# CC_v00.net
KiCad netlist of a schematic drawn in Altium Designer
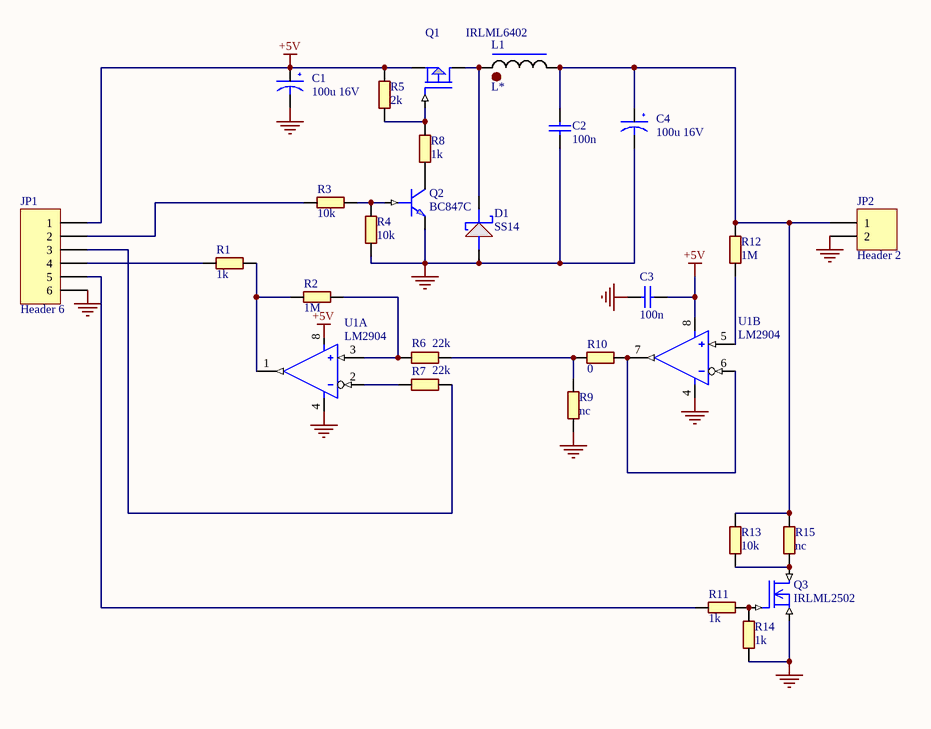
[diagram p0: CC_v00.SchDoc]

(export (version "E")
  (design (tool "Eeschema 10.0.6"))
  (components
    (comp (ref "C1")
      (value "100u 16V")
      (footprint "CAPPRD200W50D600H1250")
      (libsource (lib "Discrete") (part "C-EL-DIP"))
    )
    (comp (ref "C2") (value "100n") (footprint "CAPC1608X08N") (libsource (lib "Discrete") (part "CAPN")))
    (comp (ref "C3") (value "100n") (footprint "CAPC1608X08N") (libsource (lib "Discrete") (part "CAPN")))
    (comp (ref "C4")
      (value "100u 16V")
      (footprint "CAPPRD200W50D600H1250")
      (libsource (lib "Discrete") (part "C-EL-DIP"))
    )
    (comp (ref "D1")
      (value "SS14")
      (footprint "DIOM521X260X241L114X145N")
      (libsource (lib "Discrete") (part "DIODE SCHOTTKY"))
    )
    (comp (ref "JP1")
      (value "Header 6")
      (footprint "HDRV6W70P254_6X1_1397X254H754")
      (description "Header, 6-Pin")
      (fields (field (name "PUBLISHER") "Altium Limited"))
      (libsource (lib "Miscellaneous Connectors") (part "Header 6"))
    )
    (comp (ref "JP2")
      (value "Header 2")
      (footprint "HDRV2W64P254_2X1_508X254H854")
      (description "Header, 2-Pin")
      (fields (field (name "PUBLISHER") "Altium Limited"))
      (libsource (lib "Miscellaneous Connectors") (part "Header 2"))
    )
    (comp (ref "L1") (value "L*") (footprint "SND-0705") (libsource (lib "Discrete") (part "L*")))
    (comp (ref "Q1") (value "IRLML6402") (footprint "SOT-23") (libsource (lib "Discrete") (part "MOSF-P")))
    (comp (ref "Q2")
      (value "BC847C")
      (footprint "SOT95P245X110-3N")
      (libsource (lib "Discrete") (part "NPN"))
    )
    (comp (ref "Q3")
      (value "IRLML2502")
      (footprint "SOT95P245X110-3N")
      (libsource (lib "Discrete") (part "MFET N"))
    )
    (comp (ref "R1") (value "1k") (footprint "RESC1608X06N") (libsource (lib "Discrete") (part "RES")))
    (comp (ref "R2") (value "1M") (footprint "RESC1608X06N") (libsource (lib "Discrete") (part "RES")))
    (comp (ref "R3") (value "10k") (footprint "RESC1608X06N") (libsource (lib "Discrete") (part "RES")))
    (comp (ref "R4") (value "10k") (footprint "RESC1608X06N") (libsource (lib "") (part "RES_1")))
    (comp (ref "R5") (value "2k") (footprint "RESC1608X06N") (libsource (lib "") (part "RES_2")))
    (comp (ref "R6") (value "22k") (footprint "RESC1608X06N") (libsource (lib "Discrete") (part "RES")))
    (comp (ref "R7") (value "22k") (footprint "RESC1608X06N") (libsource (lib "Discrete") (part "RES")))
    (comp (ref "R8") (value "1k") (footprint "RESC1608X06N") (libsource (lib "") (part "RES_2")))
    (comp (ref "R9") (value "nc") (footprint "RESC1608X06N") (libsource (lib "") (part "RES_1")))
    (comp (ref "R10") (value "0") (footprint "RESC1608X06N") (libsource (lib "Discrete") (part "RES")))
    (comp (ref "R11") (value "1k") (footprint "RESC1608X06N") (libsource (lib "Discrete") (part "RES")))
    (comp (ref "R12") (value "1M") (footprint "RESC1608X06N") (libsource (lib "") (part "RES_2")))
    (comp (ref "R13") (value "10k") (footprint "RESC1608X06N") (libsource (lib "") (part "RES_2")))
    (comp (ref "R14") (value "1k") (footprint "RESC1608X06N") (libsource (lib "") (part "RES_2")))
    (comp (ref "R15") (value "nc") (footprint "RESC1608X06N") (libsource (lib "") (part "RES_2")))
    (comp (ref "U1")
      (value "LM2904")
      (footprint "SOIC127P600X175-8N")
      (description "2 Operation amplifier")
      (libsource (lib "ICs") (part "LM2904"))
    )
  )
  (nets
    (net (code "1") (name "+5V") (class "Default")
      (node (ref "C1") (pin "2") (pinfunction "+_2") (pintype "passive"))
      (node (ref "C3") (pin "2") (pinfunction "2_2") (pintype "passive"))
      (node (ref "JP1") (pin "1") (pinfunction "1_1") (pintype "passive"))
      (node (ref "Q1") (pin "3") (pinfunction "SOURCE_3") (pintype "passive"))
      (node (ref "R5") (pin "2") (pinfunction "2_2") (pintype "passive"))
      (node (ref "U1") (pin "8") (pinfunction "V+_8") (pintype "passive"))
    )
    (net (code "2") (name "GND") (class "Default")
      (node (ref "C1") (pin "1") (pinfunction "-_1") (pintype "passive"))
      (node (ref "C2") (pin "2") (pinfunction "2_2") (pintype "passive"))
      (node (ref "C3") (pin "1") (pinfunction "1_1") (pintype "passive"))
      (node (ref "C4") (pin "1") (pinfunction "-_1") (pintype "passive"))
      (node (ref "D1") (pin "A") (pinfunction "A_A") (pintype "passive"))
      (node (ref "JP1") (pin "6") (pinfunction "6_6") (pintype "passive"))
      (node (ref "JP2") (pin "2") (pinfunction "2_2") (pintype "passive"))
      (node (ref "Q2") (pin "3") (pinfunction "EMITTER_3") (pintype "passive"))
      (node (ref "Q3") (pin "3") (pinfunction "S_3") (pintype "input"))
      (node (ref "R14") (pin "1") (pinfunction "1_1") (pintype "passive"))
      (node (ref "R4") (pin "2") (pinfunction "2_2") (pintype "passive"))
      (node (ref "R9") (pin "2") (pinfunction "2_2") (pintype "passive"))
      (node (ref "U1") (pin "4") (pinfunction "V-_4") (pintype "power_in"))
    )
    (net (code "3") (name "Net-(C4-+)") (class "Default")
      (node (ref "C2") (pin "1") (pinfunction "1_1") (pintype "passive"))
      (node (ref "C4") (pin "2") (pinfunction "+_2") (pintype "passive"))
      (node (ref "JP2") (pin "1") (pinfunction "1_1") (pintype "passive"))
      (node (ref "L1") (pin "2") (pinfunction "2_2") (pintype "passive"))
      (node (ref "R12") (pin "2") (pinfunction "2_2") (pintype "passive"))
      (node (ref "R13") (pin "2") (pinfunction "2_2") (pintype "passive"))
      (node (ref "R15") (pin "2") (pinfunction "2_2") (pintype "passive"))
    )
    (net (code "4") (name "Net-(JP1-Pad2)") (class "Default")
      (node (ref "JP1") (pin "2") (pinfunction "2_2") (pintype "passive"))
      (node (ref "R3") (pin "2") (pinfunction "2_2") (pintype "passive"))
    )
    (net (code "5") (name "Net-(JP1-Pad3)") (class "Default")
      (node (ref "JP1") (pin "3") (pinfunction "3_3") (pintype "passive"))
      (node (ref "R7") (pin "1") (pinfunction "1_1") (pintype "passive"))
    )
    (net (code "6") (name "Net-(JP1-Pad4)") (class "Default")
      (node (ref "JP1") (pin "4") (pinfunction "4_4") (pintype "passive"))
      (node (ref "R1") (pin "2") (pinfunction "2_2") (pintype "passive"))
    )
    (net (code "7") (name "Net-(JP1-Pad5)") (class "Default")
      (node (ref "JP1") (pin "5") (pinfunction "5_5") (pintype "passive"))
      (node (ref "R11") (pin "2") (pinfunction "2_2") (pintype "passive"))
    )
    (net (code "8") (name "Net-(Q1-DRAIN)") (class "Default")
      (node (ref "D1") (pin "K") (pinfunction "K_K") (pintype "passive"))
      (node (ref "L1") (pin "1") (pinfunction "1_1") (pintype "passive"))
      (node (ref "Q1") (pin "2") (pinfunction "DRAIN_2") (pintype "passive"))
    )
    (net (code "9") (name "Net-(Q1-GATE)") (class "Default")
      (node (ref "Q1") (pin "1") (pinfunction "GATE_1") (pintype "input"))
      (node (ref "R5") (pin "1") (pinfunction "1_1") (pintype "passive"))
      (node (ref "R8") (pin "2") (pinfunction "2_2") (pintype "passive"))
    )
    (net (code "10") (name "Net-(Q2-BASE)") (class "Default")
      (node (ref "Q2") (pin "1") (pinfunction "BASE_1") (pintype "input"))
      (node (ref "R3") (pin "1") (pinfunction "1_1") (pintype "passive"))
      (node (ref "R4") (pin "1") (pinfunction "1_1") (pintype "passive"))
    )
    (net (code "11") (name "Net-(Q2-COLLECTOR)") (class "Default")
      (node (ref "Q2") (pin "2") (pinfunction "COLLECTOR_2") (pintype "passive"))
      (node (ref "R8") (pin "1") (pinfunction "1_1") (pintype "passive"))
    )
    (net (code "12") (name "Net-(Q3-D)") (class "Default")
      (node (ref "Q3") (pin "2") (pinfunction "D_2") (pintype "input"))
      (node (ref "R13") (pin "1") (pinfunction "1_1") (pintype "passive"))
      (node (ref "R15") (pin "1") (pinfunction "1_1") (pintype "passive"))
    )
    (net (code "13") (name "Net-(Q3-G)") (class "Default")
      (node (ref "Q3") (pin "1") (pinfunction "G_1") (pintype "input"))
      (node (ref "R11") (pin "1") (pinfunction "1_1") (pintype "passive"))
      (node (ref "R14") (pin "2") (pinfunction "2_2") (pintype "passive"))
    )
    (net (code "14") (name "Net-(R10-Pad2)") (class "Default")
      (node (ref "R10") (pin "2") (pinfunction "2_2") (pintype "passive"))
      (node (ref "R6") (pin "1") (pinfunction "1_1") (pintype "passive"))
      (node (ref "R9") (pin "1") (pinfunction "1_1") (pintype "passive"))
    )
    (net (code "15") (name "Net-(U1A-+IN)") (class "Default")
      (node (ref "R2") (pin "1") (pinfunction "1_1") (pintype "passive"))
      (node (ref "R6") (pin "2") (pinfunction "2_2") (pintype "passive"))
      (node (ref "U1") (pin "3") (pinfunction "+IN_3") (pintype "input"))
    )
    (net (code "16") (name "Net-(U1A--IN)") (class "Default")
      (node (ref "R7") (pin "2") (pinfunction "2_2") (pintype "passive"))
      (node (ref "U1") (pin "2") (pinfunction "-IN_2") (pintype "input"))
    )
    (net (code "17") (name "Net-(U1A-OUT)") (class "Default")
      (node (ref "R1") (pin "1") (pinfunction "1_1") (pintype "passive"))
      (node (ref "R2") (pin "2") (pinfunction "2_2") (pintype "passive"))
      (node (ref "U1") (pin "1") (pinfunction "OUT_1") (pintype "output"))
    )
    (net (code "18") (name "Net-(U1B-+IN)") (class "Default")
      (node (ref "R12") (pin "1") (pinfunction "1_1") (pintype "passive"))
      (node (ref "U1") (pin "5") (pinfunction "+IN_5") (pintype "input"))
    )
    (net (code "19") (name "Net-(U1B--IN)") (class "Default")
      (node (ref "R10") (pin "1") (pinfunction "1_1") (pintype "passive"))
      (node (ref "U1") (pin "6") (pinfunction "-IN_6") (pintype "input"))
      (node (ref "U1") (pin "7") (pinfunction "OUT_7") (pintype "output"))
    )
    (net (code "20") (name "unconnected-(U1A-V+-Pad8)") (class "Default")
      (node (ref "U1") (pin "8") (pinfunction "V+_8") (pintype "power_in"))
    )
  )
)
